# schematic.net
KiCad netlist of a schematic drawn in Altium Designer
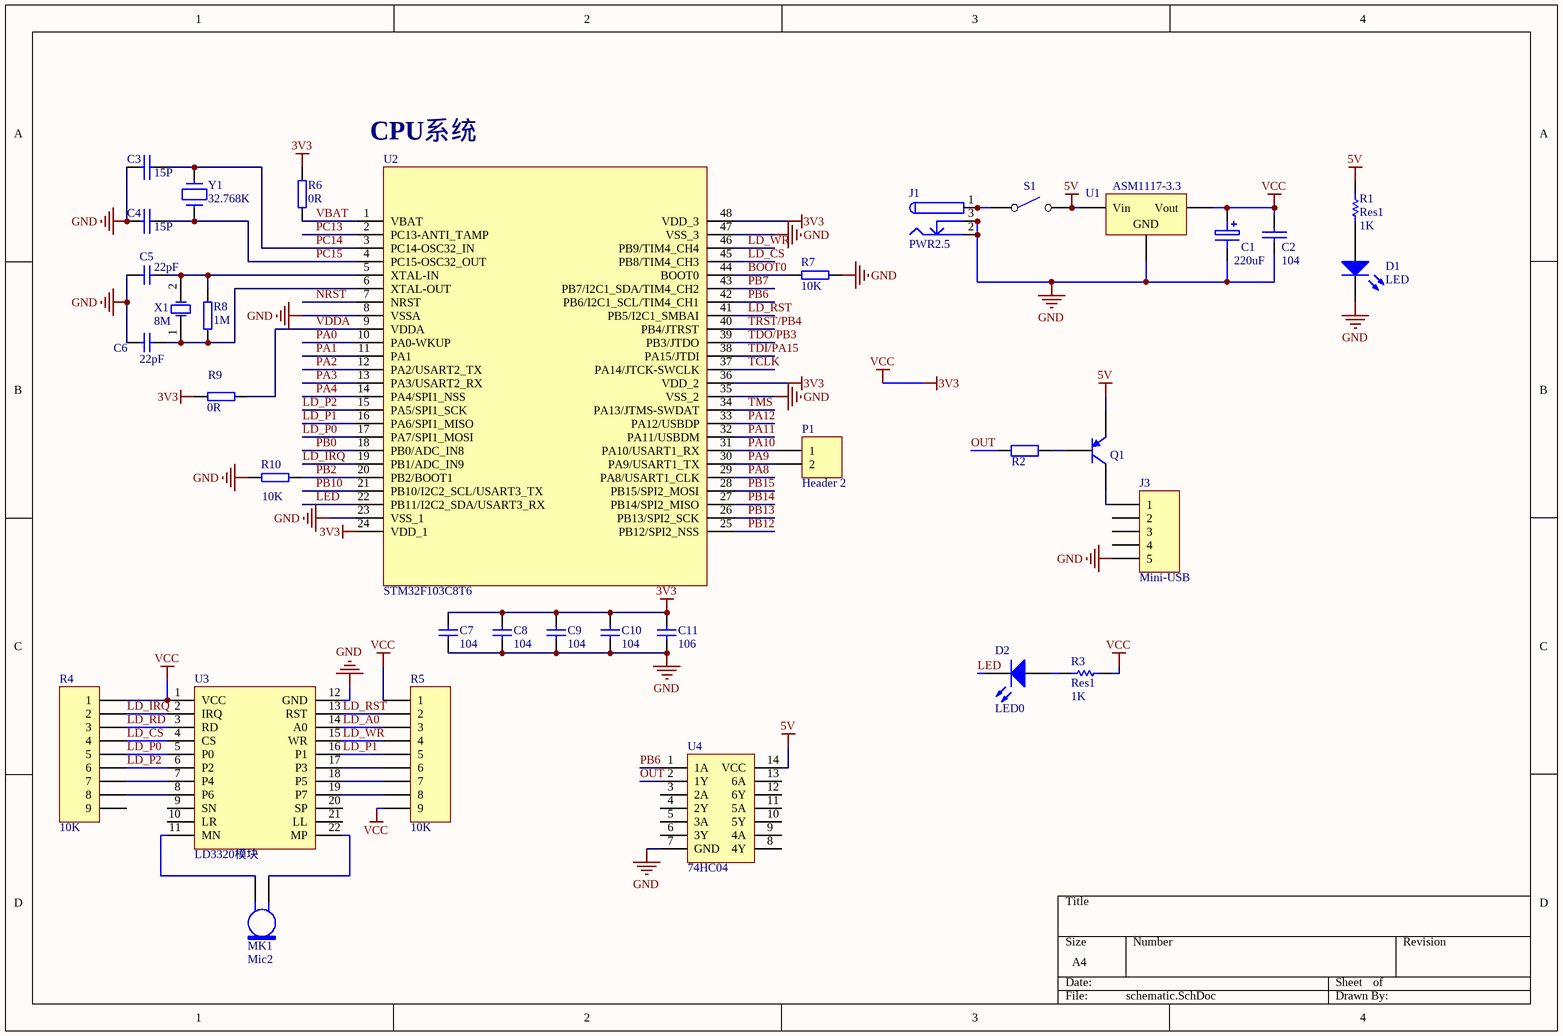
[diagram p0: schematic.SchDoc]

(export (version "E")
  (design (tool "Eeschema 10.0.6"))
  (components
    (comp (ref "C1")
      (value "220uF")
      (footprint "C0805")
      (description "10uF")
      (libsource (lib "常用元件") (part "有极性电容"))
    )
    (comp (ref "C2")
      (value "104")
      (footprint "C0805")
      (description "30pF")
      (libsource (lib "常用元件") (part "无极性电容"))
    )
    (comp (ref "C3") (value "15P") (footprint "C0805") (libsource (lib "*") (part "CAP")))
    (comp (ref "C4") (value "15P") (footprint "C0805") (libsource (lib "*") (part "CAP")))
    (comp (ref "C5")
      (value "22pF")
      (footprint "C0805")
      (description "Capacitor")
      (fields (field (name "PUBLISHER") "ZL_A0OFFICE"))
      (libsource (lib "CommomDevices") (part "CAP1"))
    )
    (comp (ref "C6")
      (value "22pF")
      (footprint "C0805")
      (description "Capacitor")
      (fields (field (name "PUBLISHER") "ZL_A0OFFICE"))
      (libsource (lib "CommomDevices") (part "CAP1"))
    )
    (comp (ref "C7")
      (value "104")
      (footprint "C0805")
      (description "Capacitor")
      (fields (field (name "PUBLISHER") "ZL_A0OFFICE"))
      (libsource (lib "CommomDevices") (part "CAP1"))
    )
    (comp (ref "C8")
      (value "104")
      (footprint "C0805")
      (description "Capacitor")
      (fields (field (name "PUBLISHER") "ZL_A0OFFICE"))
      (libsource (lib "CommomDevices") (part "CAP1"))
    )
    (comp (ref "C9")
      (value "104")
      (footprint "C0805")
      (description "Capacitor")
      (fields (field (name "PUBLISHER") "ZL_A0OFFICE"))
      (libsource (lib "CommomDevices") (part "CAP1"))
    )
    (comp (ref "C10")
      (value "104")
      (footprint "C0805")
      (description "Capacitor")
      (fields (field (name "PUBLISHER") "ZL_A0OFFICE"))
      (libsource (lib "CommomDevices") (part "CAP1"))
    )
    (comp (ref "C11")
      (value "106")
      (footprint "C0805")
      (description "Capacitor")
      (fields (field (name "PUBLISHER") "ZL_A0OFFICE"))
      (libsource (lib "CommomDevices") (part "CAP1"))
    )
    (comp (ref "D1")
      (value "LED")
      (footprint "LED_0805")
      (description "Typical INFRARED GaAs LED")
      (fields (field (name "PUBLISHER") "Altium Limited"))
      (libsource (lib "Miscellaneous Devices") (part "LED0"))
    )
    (comp (ref "D2")
      (value "LED0")
      (footprint "LED_0805")
      (description "Typical INFRARED GaAs LED")
      (fields (field (name "PUBLISHER") "Altium Limited"))
      (libsource (lib "Miscellaneous Devices") (part "LED0"))
    )
    (comp (ref "J1")
      (value "PWR2.5")
      (footprint "DC-005")
      (description "Low Voltage Power Supply Connector")
      (fields (field (name "PUBLISHER") "Altium Limited"))
      (libsource (lib "Miscellaneous Connectors") (part "PWR2.5"))
    )
    (comp (ref "J3")
      (value "Mini-USB")
      (footprint "USB1 - duplicate")
      (description "Header, 5-Pin")
      (libsource (lib "Miscellaneous Connectors") (part "Header 5"))
    )
    (comp (ref "MK1")
      (value "Mic2")
      (footprint "PIN2")
      (description "Microphone")
      (fields (field (name "PUBLISHER") "Altium Limited"))
      (libsource (lib "Miscellaneous Devices") (part "Mic2"))
    )
    (comp (ref "P1")
      (value "Header 2")
      (footprint "HDR1X2")
      (description "Header, 2-Pin")
      (fields (field (name "PUBLISHER") "Altium Limited"))
      (libsource (lib "Miscellaneous Connectors") (part "Header 2"))
    )
    (comp (ref "Q1")
      (value "S8550")
      (footprint "SOT-23")
      (description "PNP三极管")
      (libsource (lib "常用元件") (part "PNP"))
    )
    (comp (ref "R1")
      (value "Res1")
      (footprint "R0805")
      (description "Resistor")
      (fields (field (name "ALTIUM_VALUE") "1K") (field (name "PUBLISHER") "Altium Limited"))
      (libsource (lib "Miscellaneous Devices") (part "Res1"))
    )
    (comp (ref "R2")
      (value "200R")
      (footprint "R0805")
      (description "DIP")
      (libsource (lib "常用元件") (part "Resistor"))
    )
    (comp (ref "R3")
      (value "Res1")
      (footprint "R0805")
      (description "Resistor")
      (fields (field (name "ALTIUM_VALUE") "1K") (field (name "PUBLISHER") "Altium Limited"))
      (libsource (lib "Miscellaneous Devices") (part "Res1"))
    )
    (comp (ref "R4")
      (value "10K")
      (footprint "HDR1X9")
      (description "Header, 9-Pin")
      (fields (field (name "PUBLISHER") "Altium Limited"))
      (libsource (lib "Miscellaneous Connectors") (part "Header 9"))
    )
    (comp (ref "R5")
      (value "10K")
      (footprint "HDR1X9")
      (description "Header, 9-Pin")
      (fields (field (name "PUBLISHER") "Altium Limited"))
      (libsource (lib "") (part "Header 9_1"))
    )
    (comp (ref "R6") (value "0R") (footprint "R0805") (libsource (lib "ZIBO V2.0_Main") (part "R")))
    (comp (ref "R7") (value "10K") (footprint "R0805") (libsource (lib "ZIBO V2.0_Main") (part "R")))
    (comp (ref "R8") (value "1M") (footprint "R0805") (libsource (lib "ZIBO V2.0_Main") (part "R")))
    (comp (ref "R9") (value "0R") (footprint "R0805") (libsource (lib "ZIBO V2.0_Main") (part "R")))
    (comp (ref "R10") (value "10K") (footprint "R0805") (libsource (lib "ZIBO V2.0_Main") (part "R")))
    (comp (ref "S1") (value "SW-SPST") (footprint "BTN8.5*8.5") (libsource (lib "*") (part "SW-SPST")))
    (comp (ref "U1")
      (value "ASM1117-3.3")
      (footprint "SOT-223")
      (description "Voltage Regulator")
      (fields (field (name "PUBLISHER") "Altium Limited"))
      (libsource (lib "Miscellaneous Devices") (part "Volt Reg"))
    )
    (comp (ref "U2")
      (value "STM32F103C8T6")
      (footprint "48P")
      (libsource (lib "STM32_Smart") (part "STM32F103C8T6"))
    )
    (comp (ref "U3") (value "LD3320模块") (footprint "HDR2X11_CEN") (libsource (lib "BRC") (part "LD3320模块2")))
    (comp (ref "U4") (value "74HC04") (footprint "SOP14_M") (libsource (lib "BRC") (part "74HC05")))
    (comp (ref "X1")
      (value "8M")
      (footprint "XTAL")
      (description "Crystal Oscillator")
      (fields (field (name "PUBLISHER") "ZL_A0OFFICE"))
      (libsource (lib "CommomDevices") (part "XTAL_SMD"))
    )
    (comp (ref "Y1")
      (value "32.768K")
      (footprint "HDR1X2")
      (description "晶振")
      (libsource (lib "*") (part "CRYSTAL"))
    )
  )
  (nets
    (net (code "1") (name "/BOOT0") (class "Default")
      (node (ref "R7") (pin "2") (pinfunction "2_2") (pintype "passive"))
      (node (ref "U2") (pin "44") (pinfunction "BOOT0_44") (pintype "passive"))
    )
    (net (code "2") (name "/LD_A0") (class "Default")
      (node (ref "R5") (pin "3") (pinfunction "3_3") (pintype "passive"))
      (node (ref "U3") (pin "14") (pinfunction "A0_14") (pintype "passive"))
    )
    (net (code "3") (name "/LD_CS") (class "Default")
      (node (ref "R4") (pin "4") (pinfunction "4_4") (pintype "passive"))
      (node (ref "U2") (pin "45") (pinfunction "PB8/TIM4_CH3_45") (pintype "passive"))
      (node (ref "U3") (pin "4") (pinfunction "CS_4") (pintype "passive"))
    )
    (net (code "4") (name "/LD_IRQ") (class "Default")
      (node (ref "R4") (pin "2") (pinfunction "2_2") (pintype "passive"))
      (node (ref "U2") (pin "19") (pinfunction "PB1/ADC_IN9_19") (pintype "passive"))
      (node (ref "U3") (pin "2") (pinfunction "IRQ_2") (pintype "passive"))
    )
    (net (code "5") (name "/LD_P0") (class "Default")
      (node (ref "R4") (pin "5") (pinfunction "5_5") (pintype "passive"))
      (node (ref "U2") (pin "17") (pinfunction "PA7/SPI1_MOSI_17") (pintype "passive"))
      (node (ref "U3") (pin "5") (pinfunction "P0_5") (pintype "passive"))
    )
    (net (code "6") (name "/LD_P1") (class "Default")
      (node (ref "R5") (pin "5") (pinfunction "5_5") (pintype "passive"))
      (node (ref "U2") (pin "16") (pinfunction "PA6/SPI1_MISO_16") (pintype "passive"))
      (node (ref "U3") (pin "16") (pinfunction "P1_16") (pintype "passive"))
    )
    (net (code "7") (name "/LD_P2") (class "Default")
      (node (ref "R4") (pin "6") (pinfunction "6_6") (pintype "passive"))
      (node (ref "U2") (pin "15") (pinfunction "PA5/SPI1_SCK_15") (pintype "passive"))
      (node (ref "U3") (pin "6") (pinfunction "P2_6") (pintype "passive"))
    )
    (net (code "8") (name "/LD_RD") (class "Default")
      (node (ref "R4") (pin "3") (pinfunction "3_3") (pintype "passive"))
      (node (ref "U3") (pin "3") (pinfunction "RD_3") (pintype "passive"))
    )
    (net (code "9") (name "/LD_RST") (class "Default")
      (node (ref "R5") (pin "2") (pinfunction "2_2") (pintype "passive"))
      (node (ref "U2") (pin "41") (pinfunction "PB5/I2C1_SMBAI_41") (pintype "passive"))
      (node (ref "U3") (pin "13") (pinfunction "RST_13") (pintype "passive"))
    )
    (net (code "10") (name "/LD_WR") (class "Default")
      (node (ref "R5") (pin "4") (pinfunction "4_4") (pintype "passive"))
      (node (ref "U2") (pin "46") (pinfunction "PB9/TIM4_CH4_46") (pintype "passive"))
      (node (ref "U3") (pin "15") (pinfunction "WR_15") (pintype "passive"))
    )
    (net (code "11") (name "/LED") (class "Default")
      (node (ref "D2") (pin "2") (pinfunction "K_2") (pintype "passive"))
      (node (ref "U2") (pin "22") (pinfunction "PB11/I2C2_SDA/USART3_RX_22") (pintype "passive"))
    )
    (net (code "12") (name "/NRST") (class "Default")
      (node (ref "U2") (pin "7") (pinfunction "NRST_7") (pintype "passive"))
    )
    (net (code "13") (name "/OUT") (class "Default")
      (node (ref "R2") (pin "1") (pinfunction "1_1") (pintype "passive"))
      (node (ref "U4") (pin "2") (pinfunction "1Y_2") (pintype "passive"))
    )
    (net (code "14") (name "/PA0") (class "Default")
      (node (ref "U2") (pin "10") (pinfunction "PA0-WKUP_10") (pintype "passive"))
    )
    (net (code "15") (name "/PA1") (class "Default")
      (node (ref "U2") (pin "11") (pinfunction "PA1_11") (pintype "passive"))
    )
    (net (code "16") (name "/PA2") (class "Default")
      (node (ref "U2") (pin "12") (pinfunction "PA2/USART2_TX_12") (pintype "passive"))
    )
    (net (code "17") (name "/PA3") (class "Default")
      (node (ref "U2") (pin "13") (pinfunction "PA3/USART2_RX_13") (pintype "passive"))
    )
    (net (code "18") (name "/PA4") (class "Default")
      (node (ref "U2") (pin "14") (pinfunction "PA4/SPI1_NSS_14") (pintype "passive"))
    )
    (net (code "19") (name "/PA8") (class "Default")
      (node (ref "U2") (pin "29") (pinfunction "PA8/USART1_CLK_29") (pintype "passive"))
    )
    (net (code "20") (name "/PA9") (class "Default")
      (node (ref "P1") (pin "2") (pinfunction "2_2") (pintype "passive"))
      (node (ref "U2") (pin "30") (pinfunction "PA9/USART1_TX_30") (pintype "passive"))
    )
    (net (code "21") (name "/PA10") (class "Default")
      (node (ref "P1") (pin "1") (pinfunction "1_1") (pintype "passive"))
      (node (ref "U2") (pin "31") (pinfunction "PA10/USART1_RX_31") (pintype "passive"))
    )
    (net (code "22") (name "/PA11") (class "Default")
      (node (ref "U2") (pin "32") (pinfunction "PA11/USBDM_32") (pintype "passive"))
    )
    (net (code "23") (name "/PA12") (class "Default")
      (node (ref "U2") (pin "33") (pinfunction "PA12/USBDP_33") (pintype "passive"))
    )
    (net (code "24") (name "/PB0") (class "Default")
      (node (ref "U2") (pin "18") (pinfunction "PB0/ADC_IN8_18") (pintype "passive"))
    )
    (net (code "25") (name "/PB2") (class "Default")
      (node (ref "R10") (pin "1") (pinfunction "1_1") (pintype "passive"))
      (node (ref "U2") (pin "20") (pinfunction "PB2/BOOT1_20") (pintype "passive"))
    )
    (net (code "26") (name "/PB6") (class "Default")
      (node (ref "U2") (pin "42") (pinfunction "PB6/I2C1_SCL/TIM4_CH1_42") (pintype "passive"))
      (node (ref "U4") (pin "1") (pinfunction "1A_1") (pintype "passive"))
    )
    (net (code "27") (name "/PB7") (class "Default")
      (node (ref "U2") (pin "43") (pinfunction "PB7/I2C1_SDA/TIM4_CH2_43") (pintype "passive"))
    )
    (net (code "28") (name "/PB10") (class "Default")
      (node (ref "U2") (pin "21") (pinfunction "PB10/I2C2_SCL/USART3_TX_21") (pintype "passive"))
    )
    (net (code "29") (name "/PB12") (class "Default")
      (node (ref "U2") (pin "25") (pinfunction "PB12/SPI2_NSS_25") (pintype "passive"))
    )
    (net (code "30") (name "/PB13") (class "Default")
      (node (ref "U2") (pin "26") (pinfunction "PB13/SPI2_SCK_26") (pintype "passive"))
    )
    (net (code "31") (name "/PB14") (class "Default")
      (node (ref "U2") (pin "27") (pinfunction "PB14/SPI2_MISO_27") (pintype "passive"))
    )
    (net (code "32") (name "/PB15") (class "Default")
      (node (ref "U2") (pin "28") (pinfunction "PB15/SPI2_MOSI_28") (pintype "passive"))
    )
    (net (code "33") (name "/PC13") (class "Default")
      (node (ref "U2") (pin "2") (pinfunction "PC13-ANTI_TAMP_2") (pintype "passive"))
    )
    (net (code "34") (name "/PC14") (class "Default")
      (node (ref "C3") (pin "2") (pintype "passive"))
      (node (ref "U2") (pin "3") (pinfunction "PC14-OSC32_IN_3") (pintype "passive"))
      (node (ref "Y1") (pin "2") (pintype "passive"))
    )
    (net (code "35") (name "/PC15") (class "Default")
      (node (ref "C4") (pin "2") (pintype "passive"))
      (node (ref "U2") (pin "4") (pinfunction "PC15-OSC32_OUT_4") (pintype "passive"))
      (node (ref "Y1") (pin "1") (pintype "passive"))
    )
    (net (code "36") (name "/TCLK") (class "Default")
      (node (ref "U2") (pin "37") (pinfunction "PA14/JTCK-SWCLK_37") (pintype "passive"))
    )
    (net (code "37") (name "/TDI{slash}PA15") (class "Default")
      (node (ref "U2") (pin "38") (pinfunction "PA15/JTDI_38") (pintype "passive"))
    )
    (net (code "38") (name "/TDO{slash}PB3") (class "Default")
      (node (ref "U2") (pin "39") (pinfunction "PB3/JTDO_39") (pintype "passive"))
    )
    (net (code "39") (name "/TMS") (class "Default")
      (node (ref "U2") (pin "34") (pinfunction "PA13/JTMS-SWDAT_34") (pintype "passive"))
    )
    (net (code "40") (name "/TRST{slash}PB4") (class "Default")
      (node (ref "U2") (pin "40") (pinfunction "PB4/JTRST_40") (pintype "passive"))
    )
    (net (code "41") (name "/VBAT") (class "Default")
      (node (ref "R6") (pin "1") (pinfunction "1_1") (pintype "passive"))
      (node (ref "U2") (pin "1") (pinfunction "VBAT_1") (pintype "passive"))
    )
    (net (code "42") (name "/VDDA") (class "Default")
      (node (ref "R9") (pin "1") (pinfunction "1_1") (pintype "passive"))
      (node (ref "U2") (pin "9") (pinfunction "VDDA_9") (pintype "passive"))
    )
    (net (code "43") (name "3V3") (class "Default")
      (node (ref "C1") (pin "1") (pinfunction "1_1") (pintype "passive"))
      (node (ref "C10") (pin "1") (pinfunction "1_1") (pintype "passive"))
      (node (ref "C11") (pin "1") (pinfunction "1_1") (pintype "passive"))
      (node (ref "C2") (pin "1") (pinfunction "1_1") (pintype "passive"))
      (node (ref "C7") (pin "1") (pinfunction "1_1") (pintype "passive"))
      (node (ref "C8") (pin "1") (pinfunction "1_1") (pintype "passive"))
      (node (ref "C9") (pin "1") (pinfunction "1_1") (pintype "passive"))
      (node (ref "R3") (pin "2") (pinfunction "2_2") (pintype "passive"))
      (node (ref "R4") (pin "1") (pinfunction "1_1") (pintype "passive"))
      (node (ref "R5") (pin "1") (pinfunction "1_1") (pintype "passive"))
      (node (ref "R5") (pin "9") (pinfunction "9_9") (pintype "passive"))
      (node (ref "R6") (pin "2") (pinfunction "2_2") (pintype "passive"))
      (node (ref "R9") (pin "2") (pinfunction "2_2") (pintype "passive"))
      (node (ref "U1") (pin "2") (pinfunction "Vout_2") (pintype "passive"))
      (node (ref "U2") (pin "24") (pinfunction "VDD_1_24") (pintype "passive"))
      (node (ref "U2") (pin "36") (pinfunction "VDD_2_36") (pintype "passive"))
      (node (ref "U2") (pin "48") (pinfunction "VDD_3_48") (pintype "passive"))
      (node (ref "U3") (pin "1") (pinfunction "VCC_1") (pintype "passive"))
    )
    (net (code "44") (name "5V") (class "Default")
      (node (ref "Q1") (pin "2") (pinfunction "E_2") (pintype "passive"))
      (node (ref "R1") (pin "1") (pinfunction "1_1") (pintype "passive"))
      (node (ref "S1") (pin "2") (pinfunction "2_2") (pintype "passive"))
      (node (ref "U1") (pin "3") (pinfunction "Vin_3") (pintype "passive"))
      (node (ref "U4") (pin "14") (pinfunction "VCC_14") (pintype "passive"))
    )
    (net (code "45") (name "GND") (class "Default")
      (node (ref "C1") (pin "2") (pinfunction "E_2") (pintype "passive"))
      (node (ref "C10") (pin "2") (pinfunction "2_2") (pintype "passive"))
      (node (ref "C11") (pin "2") (pinfunction "2_2") (pintype "passive"))
      (node (ref "C2") (pin "2") (pinfunction "2_2") (pintype "passive"))
      (node (ref "C3") (pin "1") (pintype "passive"))
      (node (ref "C4") (pin "1") (pintype "passive"))
      (node (ref "C5") (pin "2") (pinfunction "2_2") (pintype "passive"))
      (node (ref "C6") (pin "2") (pinfunction "2_2") (pintype "passive"))
      (node (ref "C7") (pin "2") (pinfunction "2_2") (pintype "passive"))
      (node (ref "C8") (pin "2") (pinfunction "2_2") (pintype "passive"))
      (node (ref "C9") (pin "2") (pinfunction "2_2") (pintype "passive"))
      (node (ref "D1") (pin "2") (pinfunction "K_2") (pintype "passive"))
      (node (ref "J1") (pin "2") (pinfunction "2_2") (pintype "power_in"))
      (node (ref "J1") (pin "2A") (pinfunction "2A_2A") (pintype "power_in"))
      (node (ref "J1") (pin "2B") (pinfunction "2B_2B") (pintype "power_in"))
      (node (ref "J1") (pin "3") (pinfunction "3_3") (pintype "power_in"))
      (node (ref "J1") (pin "3A") (pinfunction "3A_3A") (pintype "power_in"))
      (node (ref "J1") (pin "3B") (pinfunction "3B_3B") (pintype "power_in"))
      (node (ref "J3") (pin "5") (pinfunction "5_5") (pintype "passive"))
      (node (ref "R10") (pin "2") (pinfunction "2_2") (pintype "passive"))
      (node (ref "R7") (pin "1") (pinfunction "1_1") (pintype "passive"))
      (node (ref "U1") (pin "1") (pinfunction "GND_1") (pintype "passive"))
      (node (ref "U2") (pin "23") (pinfunction "VSS_1_23") (pintype "passive"))
      (node (ref "U2") (pin "35") (pinfunction "VSS_2_35") (pintype "passive"))
      (node (ref "U2") (pin "47") (pinfunction "VSS_3_47") (pintype "passive"))
      (node (ref "U2") (pin "8") (pinfunction "VSSA_8") (pintype "passive"))
      (node (ref "U3") (pin "12") (pinfunction "GND_12") (pintype "passive"))
      (node (ref "U4") (pin "7") (pinfunction "GND_7") (pintype "passive"))
    )
    (net (code "46") (name "Net-(D1-A)") (class "Default")
      (node (ref "D1") (pin "1") (pinfunction "A_1") (pintype "passive"))
      (node (ref "R1") (pin "2") (pinfunction "2_2") (pintype "passive"))
    )
    (net (code "47") (name "Net-(D2-A)") (class "Default")
      (node (ref "D2") (pin "1") (pinfunction "A_1") (pintype "passive"))
      (node (ref "R3") (pin "1") (pinfunction "1_1") (pintype "passive"))
    )
    (net (code "48") (name "Net-(J1-Pad1)") (class "Default")
      (node (ref "J1") (pin "1") (pinfunction "1_1") (pintype "power_in"))
      (node (ref "J1") (pin "1A") (pinfunction "1A_1A") (pintype "power_in"))
      (node (ref "J1") (pin "1B") (pinfunction "1B_1B") (pintype "power_in"))
      (node (ref "S1") (pin "3") (pinfunction "3_3") (pintype "passive"))
    )
    (net (code "49") (name "Net-(J3-Pad1)") (class "Default")
      (node (ref "J3") (pin "1") (pinfunction "1_1") (pintype "passive"))
      (node (ref "Q1") (pin "3") (pinfunction "3_3") (pintype "passive"))
    )
    (net (code "50") (name "Net-(Q1-B)") (class "Default")
      (node (ref "Q1") (pin "1") (pinfunction "B_1") (pintype "passive"))
      (node (ref "R2") (pin "2") (pinfunction "2_2") (pintype "passive"))
    )
    (net (code "51") (name "Net-(U2-XTAL-IN)") (class "Default")
      (node (ref "C5") (pin "1") (pinfunction "1_1") (pintype "passive"))
      (node (ref "R8") (pin "2") (pinfunction "2_2") (pintype "passive"))
      (node (ref "U2") (pin "5") (pinfunction "XTAL-IN_5") (pintype "passive"))
      (node (ref "X1") (pin "2") (pinfunction "2_2") (pintype "passive"))
    )
    (net (code "52") (name "Net-(U2-XTAL-OUT)") (class "Default")
      (node (ref "C6") (pin "1") (pinfunction "1_1") (pintype "passive"))
      (node (ref "R8") (pin "1") (pinfunction "1_1") (pintype "passive"))
      (node (ref "U2") (pin "6") (pinfunction "XTAL-OUT_6") (pintype "passive"))
      (node (ref "X1") (pin "1") (pinfunction "1_1") (pintype "passive"))
    )
    (net (code "53") (name "Net-(U3-MN)") (class "Default")
      (node (ref "MK1") (pin "2") (pinfunction "2_2") (pintype "passive"))
      (node (ref "U3") (pin "11") (pinfunction "MN_11") (pintype "passive"))
    )
    (net (code "54") (name "Net-(U3-MP)") (class "Default")
      (node (ref "MK1") (pin "1") (pinfunction "1_1") (pintype "passive"))
      (node (ref "U3") (pin "22") (pinfunction "MP_22") (pintype "passive"))
    )
    (net (code "55") (name "Net-(U3-P3)") (class "Default")
      (node (ref "R5") (pin "6") (pinfunction "6_6") (pintype "passive"))
      (node (ref "U3") (pin "17") (pinfunction "P3_17") (pintype "passive"))
    )
    (net (code "56") (name "Net-(U3-P4)") (class "Default")
      (node (ref "R4") (pin "7") (pinfunction "7_7") (pintype "passive"))
      (node (ref "U3") (pin "7") (pinfunction "P4_7") (pintype "passive"))
    )
    (net (code "57") (name "Net-(U3-P5)") (class "Default")
      (node (ref "R5") (pin "7") (pinfunction "7_7") (pintype "passive"))
      (node (ref "U3") (pin "18") (pinfunction "P5_18") (pintype "passive"))
    )
    (net (code "58") (name "Net-(U3-P6)") (class "Default")
      (node (ref "R4") (pin "8") (pinfunction "8_8") (pintype "passive"))
      (node (ref "U3") (pin "8") (pinfunction "P6_8") (pintype "passive"))
    )
    (net (code "59") (name "Net-(U3-P7)") (class "Default")
      (node (ref "R5") (pin "8") (pinfunction "8_8") (pintype "passive"))
      (node (ref "U3") (pin "19") (pinfunction "P7_19") (pintype "passive"))
    )
    (net (code "60") (name "unconnected-(J3-Pad2)") (class "Default")
      (node (ref "J3") (pin "2") (pinfunction "2_2") (pintype "passive"))
    )
    (net (code "61") (name "unconnected-(J3-Pad3)") (class "Default")
      (node (ref "J3") (pin "3") (pinfunction "3_3") (pintype "passive"))
    )
    (net (code "62") (name "unconnected-(J3-Pad4)") (class "Default")
      (node (ref "J3") (pin "4") (pinfunction "4_4") (pintype "passive"))
    )
    (net (code "63") (name "unconnected-(R4-Pad9)") (class "Default")
      (node (ref "R4") (pin "9") (pinfunction "9_9") (pintype "passive"))
    )
    (net (code "64") (name "unconnected-(U3-LL-Pad21)") (class "Default")
      (node (ref "U3") (pin "21") (pinfunction "LL_21") (pintype "passive"))
    )
    (net (code "65") (name "unconnected-(U3-LR-Pad10)") (class "Default")
      (node (ref "U3") (pin "10") (pinfunction "LR_10") (pintype "passive"))
    )
    (net (code "66") (name "unconnected-(U3-SN-Pad9)") (class "Default")
      (node (ref "U3") (pin "9") (pinfunction "SN_9") (pintype "passive"))
    )
    (net (code "67") (name "unconnected-(U3-SP-Pad20)") (class "Default")
      (node (ref "U3") (pin "20") (pinfunction "SP_20") (pintype "passive"))
    )
    (net (code "68") (name "unconnected-(U4-2A-Pad3)") (class "Default")
      (node (ref "U4") (pin "3") (pinfunction "2A_3") (pintype "passive"))
    )
    (net (code "69") (name "unconnected-(U4-2Y-Pad4)") (class "Default")
      (node (ref "U4") (pin "4") (pinfunction "2Y_4") (pintype "passive"))
    )
    (net (code "70") (name "unconnected-(U4-3A-Pad5)") (class "Default")
      (node (ref "U4") (pin "5") (pinfunction "3A_5") (pintype "passive"))
    )
    (net (code "71") (name "unconnected-(U4-3Y-Pad6)") (class "Default")
      (node (ref "U4") (pin "6") (pinfunction "3Y_6") (pintype "passive"))
    )
    (net (code "72") (name "unconnected-(U4-4A-Pad9)") (class "Default")
      (node (ref "U4") (pin "9") (pinfunction "4A_9") (pintype "passive"))
    )
    (net (code "73") (name "unconnected-(U4-4Y-Pad8)") (class "Default")
      (node (ref "U4") (pin "8") (pinfunction "4Y_8") (pintype "passive"))
    )
    (net (code "74") (name "unconnected-(U4-5A-Pad11)") (class "Default")
      (node (ref "U4") (pin "11") (pinfunction "5A_11") (pintype "passive"))
    )
    (net (code "75") (name "unconnected-(U4-5Y-Pad10)") (class "Default")
      (node (ref "U4") (pin "10") (pinfunction "5Y_10") (pintype "passive"))
    )
    (net (code "76") (name "unconnected-(U4-6A-Pad13)") (class "Default")
      (node (ref "U4") (pin "13") (pinfunction "6A_13") (pintype "passive"))
    )
    (net (code "77") (name "unconnected-(U4-6Y-Pad12)") (class "Default")
      (node (ref "U4") (pin "12") (pinfunction "6Y_12") (pintype "passive"))
    )
  )
)
